# MagnetReaderDevice.net
KiCad netlist of a schematic drawn in EAGLE
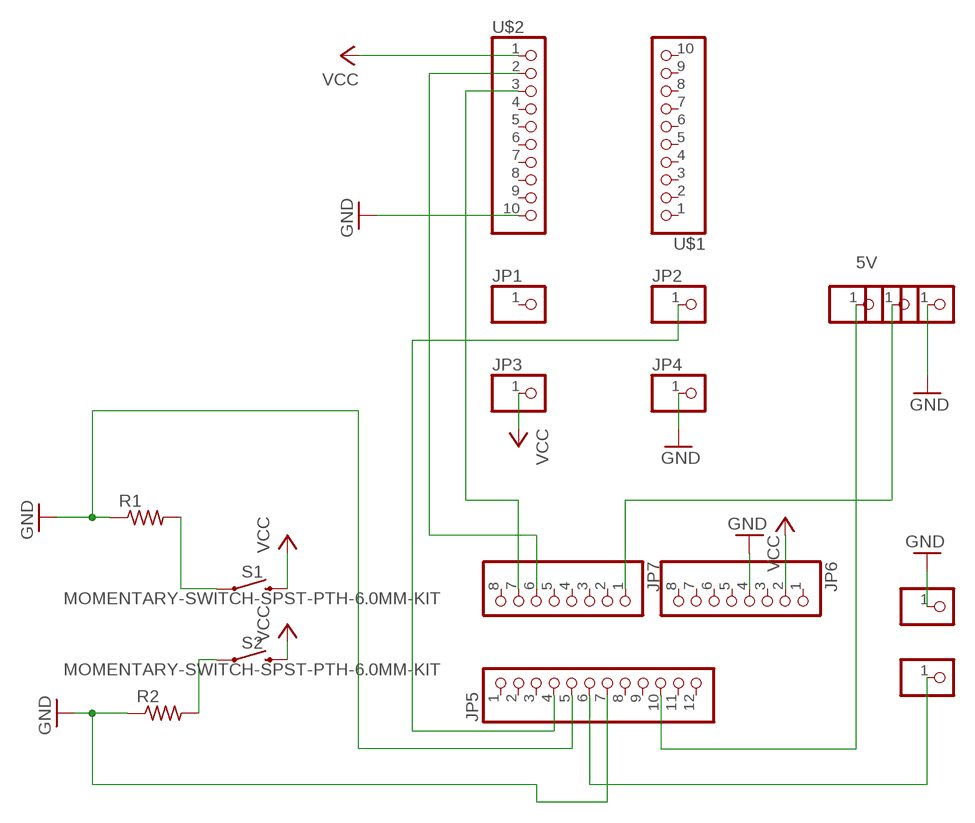
[diagram p0: schematic, sheet 1]

(export (version "E")
  (design (tool "Eeschema 10.0.6"))
  (components
    (comp (ref "5V")
      (value "PINHD-1X1CB")
      (footprint "eagle-import:1X01-CLEANBIG")
      (libsource (lib "eagle-import") (part "PINHD-1X1CB"))
    )
    (comp (ref "BZ+")
      (value "PINHD-1X1CB")
      (footprint "eagle-import:1X01-CLEANBIG")
      (libsource (lib "eagle-import") (part "PINHD-1X1CB"))
    )
    (comp (ref "BZ-")
      (value "PINHD-1X1CB")
      (footprint "eagle-import:1X01-CLEANBIG")
      (libsource (lib "eagle-import") (part "PINHD-1X1CB"))
    )
    (comp (ref "DIN")
      (value "PINHD-1X1CB")
      (footprint "eagle-import:1X01-CLEANBIG")
      (libsource (lib "eagle-import") (part "PINHD-1X1CB"))
    )
    (comp (ref "JP1")
      (value "PINHD-1X1CB")
      (footprint "eagle-import:1X01-CLEANBIG")
      (libsource (lib "eagle-import") (part "PINHD-1X1CB"))
    )
    (comp (ref "JP2")
      (value "PINHD-1X1CB")
      (footprint "eagle-import:1X01-CLEANBIG")
      (libsource (lib "eagle-import") (part "PINHD-1X1CB"))
    )
    (comp (ref "JP3")
      (value "PINHD-1X1CB")
      (footprint "eagle-import:1X01-CLEANBIG")
      (libsource (lib "eagle-import") (part "PINHD-1X1CB"))
    )
    (comp (ref "JP4")
      (value "PINHD-1X1CB")
      (footprint "eagle-import:1X01-CLEANBIG")
      (libsource (lib "eagle-import") (part "PINHD-1X1CB"))
    )
    (comp (ref "JP5")
      (value "PINHD-1X12-CB")
      (footprint "eagle-import:1X12-CB")
      (libsource (lib "eagle-import") (part "PINHD-1X12-CB"))
    )
    (comp (ref "JP6")
      (value "PINHD-1X8BIG")
      (footprint "eagle-import:1X08-BIG")
      (libsource (lib "eagle-import") (part "PINHD-1X8BIG"))
    )
    (comp (ref "JP7")
      (value "PINHD-1X8BIG")
      (footprint "eagle-import:1X08-BIG")
      (libsource (lib "eagle-import") (part "PINHD-1X8BIG"))
    )
    (comp (ref "MSGND")
      (value "PINHD-1X1CB")
      (footprint "eagle-import:1X01-CLEANBIG")
      (libsource (lib "eagle-import") (part "PINHD-1X1CB"))
    )
    (comp (ref "R1")
      (value "FLIPFLOP-RES")
      (footprint "eagle-import:0805-THM")
      (libsource (lib "eagle-import") (part "FLIPFLOP-RES"))
    )
    (comp (ref "R2")
      (value "FLIPFLOP-RES")
      (footprint "eagle-import:0805-THM")
      (libsource (lib "eagle-import") (part "FLIPFLOP-RES"))
    )
    (comp (ref "S1")
      (value "MOMENTARY-SWITCH-SPST-PTH-6.0MM-KIT")
      (footprint "eagle-import:TACTILE_SWITCH_PTH_6.0MM_KIT")
      (libsource (lib "eagle-import") (part "MOMENTARY-SWITCH-SPST-PTH-6.0MM-KIT"))
    )
    (comp (ref "S2")
      (value "MOMENTARY-SWITCH-SPST-PTH-6.0MM-KIT")
      (footprint "eagle-import:TACTILE_SWITCH_PTH_6.0MM_KIT")
      (libsource (lib "eagle-import") (part "MOMENTARY-SWITCH-SPST-PTH-6.0MM-KIT"))
    )
    (comp (ref "U$1")
      (value "PINHD-1X10")
      (footprint "eagle-import:1X10-BIG")
      (libsource (lib "eagle-import") (part "PINHD-1X10"))
    )
    (comp (ref "U$2")
      (value "PINHD-1X10")
      (footprint "eagle-import:1X10-BIG")
      (libsource (lib "eagle-import") (part "PINHD-1X10"))
    )
  )
  (nets
    (net (code "1") (name "GND") (class "Default")
      (node (ref "BZ+") (pin "1") (pinfunction "1_1") (pintype "passive"))
      (node (ref "JP4") (pin "1") (pinfunction "1_1") (pintype "passive"))
      (node (ref "JP5") (pin "5") (pinfunction "5_5") (pintype "passive"))
      (node (ref "JP5") (pin "7") (pinfunction "7_7") (pintype "passive"))
      (node (ref "JP6") (pin "4") (pinfunction "4_4") (pintype "passive"))
      (node (ref "MSGND") (pin "1") (pinfunction "1_1") (pintype "passive"))
      (node (ref "R1") (pin "1") (pinfunction "1_1") (pintype "passive"))
      (node (ref "R2") (pin "1") (pinfunction "1_1") (pintype "passive"))
      (node (ref "U$2") (pin "10") (pinfunction "10_10") (pintype "passive"))
    )
    (net (code "2") (name "Net-(5V-Pad1)") (class "Default")
      (node (ref "5V") (pin "1") (pinfunction "1_1") (pintype "passive"))
      (node (ref "JP5") (pin "10") (pinfunction "10_10") (pintype "passive"))
    )
    (net (code "3") (name "Net-(BZ--Pad1)") (class "Default")
      (node (ref "BZ-") (pin "1") (pinfunction "1_1") (pintype "passive"))
      (node (ref "JP5") (pin "6") (pinfunction "6_6") (pintype "passive"))
    )
    (net (code "4") (name "Net-(DIN-Pad1)") (class "Default")
      (node (ref "DIN") (pin "1") (pinfunction "1_1") (pintype "passive"))
      (node (ref "JP7") (pin "1") (pinfunction "1_1") (pintype "passive"))
    )
    (net (code "5") (name "Net-(JP2-Pad1)") (class "Default")
      (node (ref "JP2") (pin "1") (pinfunction "1_1") (pintype "passive"))
      (node (ref "JP5") (pin "4") (pinfunction "4_4") (pintype "passive"))
    )
    (net (code "6") (name "Net-(JP7-Pad6)") (class "Default")
      (node (ref "JP7") (pin "6") (pinfunction "6_6") (pintype "passive"))
      (node (ref "U$2") (pin "2") (pinfunction "2_2") (pintype "passive"))
    )
    (net (code "7") (name "Net-(JP7-Pad7)") (class "Default")
      (node (ref "JP7") (pin "7") (pinfunction "7_7") (pintype "passive"))
      (node (ref "U$2") (pin "3") (pinfunction "3_3") (pintype "passive"))
    )
    (net (code "8") (name "Net-(R1-Pad2)") (class "Default")
      (node (ref "R1") (pin "2") (pinfunction "2_2") (pintype "passive"))
      (node (ref "S1") (pin "1") (pinfunction "1_1") (pintype "passive"))
    )
    (net (code "9") (name "Net-(R2-Pad2)") (class "Default")
      (node (ref "R2") (pin "2") (pinfunction "2_2") (pintype "passive"))
      (node (ref "S2") (pin "1") (pinfunction "1_1") (pintype "passive"))
    )
    (net (code "10") (name "VCC") (class "Default")
      (node (ref "JP3") (pin "1") (pinfunction "1_1") (pintype "passive"))
      (node (ref "JP6") (pin "2") (pinfunction "2_2") (pintype "passive"))
      (node (ref "S1") (pin "3") (pinfunction "2_3") (pintype "passive"))
      (node (ref "S2") (pin "3") (pinfunction "2_3") (pintype "passive"))
      (node (ref "U$2") (pin "1") (pinfunction "1_1") (pintype "passive"))
    )
    (net (code "11") (name "unconnected-(JP1-Pad1)") (class "Default")
      (node (ref "JP1") (pin "1") (pinfunction "1_1") (pintype "passive"))
    )
    (net (code "12") (name "unconnected-(JP5-Pad1)") (class "Default")
      (node (ref "JP5") (pin "1") (pinfunction "1_1") (pintype "passive"))
    )
    (net (code "13") (name "unconnected-(JP5-Pad2)") (class "Default")
      (node (ref "JP5") (pin "2") (pinfunction "2_2") (pintype "passive"))
    )
    (net (code "14") (name "unconnected-(JP5-Pad3)") (class "Default")
      (node (ref "JP5") (pin "3") (pinfunction "3_3") (pintype "passive"))
    )
    (net (code "15") (name "unconnected-(JP5-Pad8)") (class "Default")
      (node (ref "JP5") (pin "8") (pinfunction "8_8") (pintype "passive"))
    )
    (net (code "16") (name "unconnected-(JP5-Pad9)") (class "Default")
      (node (ref "JP5") (pin "9") (pinfunction "9_9") (pintype "passive"))
    )
    (net (code "17") (name "unconnected-(JP5-Pad11)") (class "Default")
      (node (ref "JP5") (pin "11") (pinfunction "11_11") (pintype "passive"))
    )
    (net (code "18") (name "unconnected-(JP5-Pad12)") (class "Default")
      (node (ref "JP5") (pin "12") (pinfunction "12_12") (pintype "passive"))
    )
    (net (code "19") (name "unconnected-(JP6-Pad1)") (class "Default")
      (node (ref "JP6") (pin "1") (pinfunction "1_1") (pintype "passive"))
    )
    (net (code "20") (name "unconnected-(JP6-Pad3)") (class "Default")
      (node (ref "JP6") (pin "3") (pinfunction "3_3") (pintype "passive"))
    )
    (net (code "21") (name "unconnected-(JP6-Pad5)") (class "Default")
      (node (ref "JP6") (pin "5") (pinfunction "5_5") (pintype "passive"))
    )
    (net (code "22") (name "unconnected-(JP6-Pad6)") (class "Default")
      (node (ref "JP6") (pin "6") (pinfunction "6_6") (pintype "passive"))
    )
    (net (code "23") (name "unconnected-(JP6-Pad7)") (class "Default")
      (node (ref "JP6") (pin "7") (pinfunction "7_7") (pintype "passive"))
    )
    (net (code "24") (name "unconnected-(JP6-Pad8)") (class "Default")
      (node (ref "JP6") (pin "8") (pinfunction "8_8") (pintype "passive"))
    )
    (net (code "25") (name "unconnected-(JP7-Pad2)") (class "Default")
      (node (ref "JP7") (pin "2") (pinfunction "2_2") (pintype "passive"))
    )
    (net (code "26") (name "unconnected-(JP7-Pad3)") (class "Default")
      (node (ref "JP7") (pin "3") (pinfunction "3_3") (pintype "passive"))
    )
    (net (code "27") (name "unconnected-(JP7-Pad4)") (class "Default")
      (node (ref "JP7") (pin "4") (pinfunction "4_4") (pintype "passive"))
    )
    (net (code "28") (name "unconnected-(JP7-Pad5)") (class "Default")
      (node (ref "JP7") (pin "5") (pinfunction "5_5") (pintype "passive"))
    )
    (net (code "29") (name "unconnected-(JP7-Pad8)") (class "Default")
      (node (ref "JP7") (pin "8") (pinfunction "8_8") (pintype "passive"))
    )
    (net (code "30") (name "unconnected-(U$1-Pad1)") (class "Default")
      (node (ref "U$1") (pin "1") (pinfunction "1_1") (pintype "passive"))
    )
    (net (code "31") (name "unconnected-(U$1-Pad2)") (class "Default")
      (node (ref "U$1") (pin "2") (pinfunction "2_2") (pintype "passive"))
    )
    (net (code "32") (name "unconnected-(U$1-Pad3)") (class "Default")
      (node (ref "U$1") (pin "3") (pinfunction "3_3") (pintype "passive"))
    )
    (net (code "33") (name "unconnected-(U$1-Pad4)") (class "Default")
      (node (ref "U$1") (pin "4") (pinfunction "4_4") (pintype "passive"))
    )
    (net (code "34") (name "unconnected-(U$1-Pad5)") (class "Default")
      (node (ref "U$1") (pin "5") (pinfunction "5_5") (pintype "passive"))
    )
    (net (code "35") (name "unconnected-(U$1-Pad6)") (class "Default")
      (node (ref "U$1") (pin "6") (pinfunction "6_6") (pintype "passive"))
    )
    (net (code "36") (name "unconnected-(U$1-Pad7)") (class "Default")
      (node (ref "U$1") (pin "7") (pinfunction "7_7") (pintype "passive"))
    )
    (net (code "37") (name "unconnected-(U$1-Pad8)") (class "Default")
      (node (ref "U$1") (pin "8") (pinfunction "8_8") (pintype "passive"))
    )
    (net (code "38") (name "unconnected-(U$1-Pad9)") (class "Default")
      (node (ref "U$1") (pin "9") (pinfunction "9_9") (pintype "passive"))
    )
    (net (code "39") (name "unconnected-(U$1-Pad10)") (class "Default")
      (node (ref "U$1") (pin "10") (pinfunction "10_10") (pintype "passive"))
    )
    (net (code "40") (name "unconnected-(U$2-Pad4)") (class "Default")
      (node (ref "U$2") (pin "4") (pinfunction "4_4") (pintype "passive"))
    )
    (net (code "41") (name "unconnected-(U$2-Pad5)") (class "Default")
      (node (ref "U$2") (pin "5") (pinfunction "5_5") (pintype "passive"))
    )
    (net (code "42") (name "unconnected-(U$2-Pad6)") (class "Default")
      (node (ref "U$2") (pin "6") (pinfunction "6_6") (pintype "passive"))
    )
    (net (code "43") (name "unconnected-(U$2-Pad7)") (class "Default")
      (node (ref "U$2") (pin "7") (pinfunction "7_7") (pintype "passive"))
    )
    (net (code "44") (name "unconnected-(U$2-Pad8)") (class "Default")
      (node (ref "U$2") (pin "8") (pinfunction "8_8") (pintype "passive"))
    )
    (net (code "45") (name "unconnected-(U$2-Pad9)") (class "Default")
      (node (ref "U$2") (pin "9") (pinfunction "9_9") (pintype "passive"))
    )
  )
)
